# schematic.net
KiCad netlist of a schematic drawn in EAGLE
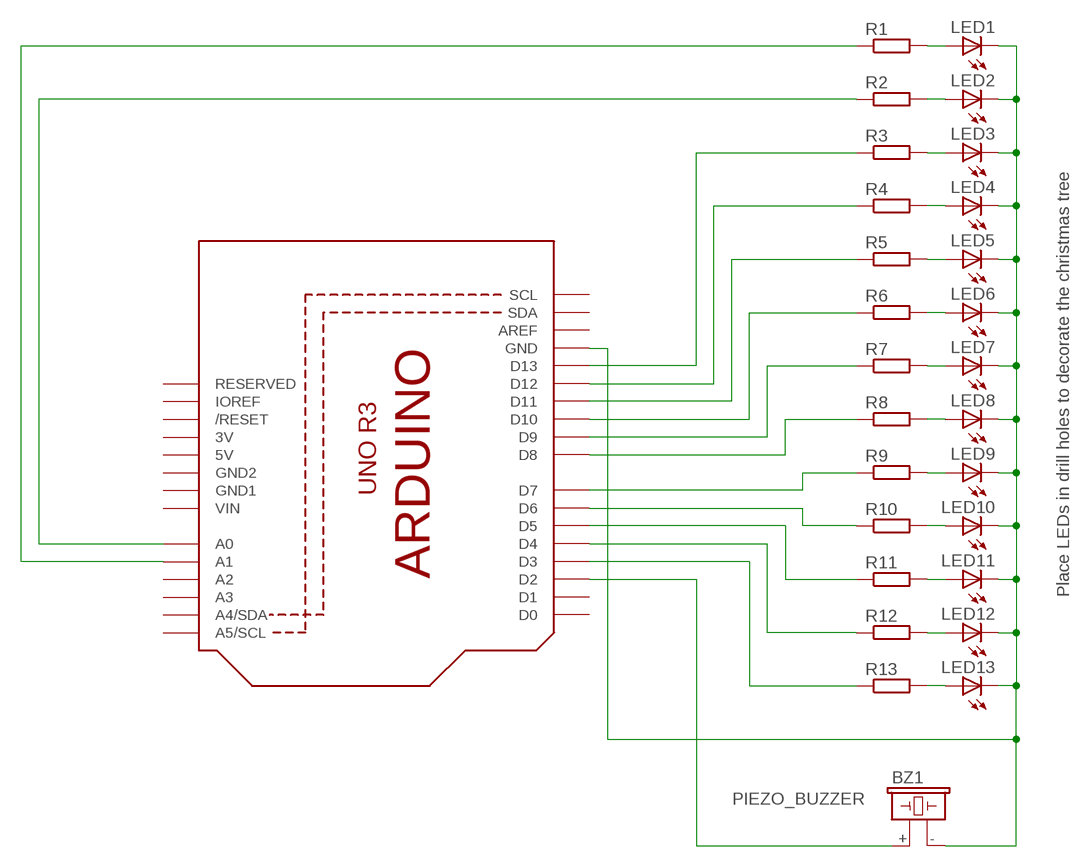
[diagram p0: schematic, sheet 1]

(export (version "E")
  (design (tool "Eeschema 10.0.6"))
  (components
    (comp (ref "BZ1")
      (value "PIEZO_BUZZER")
      (footprint "eagle-import:F_CM12P")
      (libsource (lib "eagle-import") (part "PIEZO_BUZZER"))
    )
    (comp (ref "LED1")
      (value "LED3MM")
      (footprint "eagle-import:LED3MM")
      (libsource (lib "eagle-import") (part "LED3MM"))
    )
    (comp (ref "LED2")
      (value "LED3MM")
      (footprint "eagle-import:LED3MM")
      (libsource (lib "eagle-import") (part "LED3MM"))
    )
    (comp (ref "LED3")
      (value "LED3MM")
      (footprint "eagle-import:LED3MM")
      (libsource (lib "eagle-import") (part "LED3MM"))
    )
    (comp (ref "LED4")
      (value "LED3MM")
      (footprint "eagle-import:LED3MM")
      (libsource (lib "eagle-import") (part "LED3MM"))
    )
    (comp (ref "LED5")
      (value "LED3MM")
      (footprint "eagle-import:LED3MM")
      (libsource (lib "eagle-import") (part "LED3MM"))
    )
    (comp (ref "LED6")
      (value "LED3MM")
      (footprint "eagle-import:LED3MM")
      (libsource (lib "eagle-import") (part "LED3MM"))
    )
    (comp (ref "LED7")
      (value "LED3MM")
      (footprint "eagle-import:LED3MM")
      (libsource (lib "eagle-import") (part "LED3MM"))
    )
    (comp (ref "LED8")
      (value "LED3MM")
      (footprint "eagle-import:LED3MM")
      (libsource (lib "eagle-import") (part "LED3MM"))
    )
    (comp (ref "LED9")
      (value "LED3MM")
      (footprint "eagle-import:LED3MM")
      (libsource (lib "eagle-import") (part "LED3MM"))
    )
    (comp (ref "LED10")
      (value "LED3MM")
      (footprint "eagle-import:LED3MM")
      (libsource (lib "eagle-import") (part "LED3MM"))
    )
    (comp (ref "LED11")
      (value "LED3MM")
      (footprint "eagle-import:LED3MM")
      (libsource (lib "eagle-import") (part "LED3MM"))
    )
    (comp (ref "LED12")
      (value "LED3MM")
      (footprint "eagle-import:LED3MM")
      (libsource (lib "eagle-import") (part "LED3MM"))
    )
    (comp (ref "LED13")
      (value "LED3MM")
      (footprint "eagle-import:LED3MM")
      (libsource (lib "eagle-import") (part "LED3MM"))
    )
    (comp (ref "R1")
      (value "R0204/7")
      (footprint "eagle-import:0204_7")
      (libsource (lib "eagle-import") (part "R0204/7"))
    )
    (comp (ref "R2")
      (value "R0204/7")
      (footprint "eagle-import:0204_7")
      (libsource (lib "eagle-import") (part "R0204/7"))
    )
    (comp (ref "R3")
      (value "R0204/7")
      (footprint "eagle-import:0204_7")
      (libsource (lib "eagle-import") (part "R0204/7"))
    )
    (comp (ref "R4")
      (value "R0204/7")
      (footprint "eagle-import:0204_7")
      (libsource (lib "eagle-import") (part "R0204/7"))
    )
    (comp (ref "R5")
      (value "R0204/7")
      (footprint "eagle-import:0204_7")
      (libsource (lib "eagle-import") (part "R0204/7"))
    )
    (comp (ref "R6")
      (value "R0204/7")
      (footprint "eagle-import:0204_7")
      (libsource (lib "eagle-import") (part "R0204/7"))
    )
    (comp (ref "R7")
      (value "R0204/7")
      (footprint "eagle-import:0204_7")
      (libsource (lib "eagle-import") (part "R0204/7"))
    )
    (comp (ref "R8")
      (value "R0204/7")
      (footprint "eagle-import:0204_7")
      (libsource (lib "eagle-import") (part "R0204/7"))
    )
    (comp (ref "R9")
      (value "R0204/7")
      (footprint "eagle-import:0204_7")
      (libsource (lib "eagle-import") (part "R0204/7"))
    )
    (comp (ref "R10")
      (value "R0204/7")
      (footprint "eagle-import:0204_7")
      (libsource (lib "eagle-import") (part "R0204/7"))
    )
    (comp (ref "R11")
      (value "R0204/7")
      (footprint "eagle-import:0204_7")
      (libsource (lib "eagle-import") (part "R0204/7"))
    )
    (comp (ref "R12")
      (value "R0204/7")
      (footprint "eagle-import:0204_7")
      (libsource (lib "eagle-import") (part "R0204/7"))
    )
    (comp (ref "R13")
      (value "R0204/7")
      (footprint "eagle-import:0204_7")
      (libsource (lib "eagle-import") (part "R0204/7"))
    )
    (comp (ref "U1")
      (value "ARDUINOR3-BPLACE")
      (footprint "eagle-import:ARDUINOR3-BPLACE")
      (libsource (lib "eagle-import") (part "ARDUINOR3-BPLACE"))
    )
  )
  (nets
    (net (code "1") (name "/3V") (class "Default")
      (node (ref "U1") (pin "3V") (pinfunction "3V_3V") (pintype "power_in"))
    )
    (net (code "2") (name "/5V") (class "Default")
      (node (ref "U1") (pin "5V") (pinfunction "5V_5V") (pintype "power_in"))
    )
    (net (code "3") (name "/GND1") (class "Default")
      (node (ref "U1") (pin "GND1") (pinfunction "GND1_GND1") (pintype "power_in"))
    )
    (net (code "4") (name "/GND2") (class "Default")
      (node (ref "U1") (pin "GND2") (pinfunction "GND2_GND2") (pintype "power_in"))
    )
    (net (code "5") (name "/VIN") (class "Default")
      (node (ref "U1") (pin "VIN") (pinfunction "VIN_VIN") (pintype "power_in"))
    )
    (net (code "6") (name "Net-(BZ1-1)") (class "Default")
      (node (ref "BZ1") (pin "+") (pinfunction "1_+") (pintype "passive"))
      (node (ref "U1") (pin "D2") (pinfunction "D2_D2") (pintype "bidirectional"))
    )
    (net (code "7") (name "Net-(BZ1-2)") (class "Default")
      (node (ref "BZ1") (pin "-") (pinfunction "2_-") (pintype "passive"))
      (node (ref "LED1") (pin "K") (pinfunction "C_K") (pintype "passive"))
      (node (ref "LED10") (pin "K") (pinfunction "C_K") (pintype "passive"))
      (node (ref "LED11") (pin "K") (pinfunction "C_K") (pintype "passive"))
      (node (ref "LED12") (pin "K") (pinfunction "C_K") (pintype "passive"))
      (node (ref "LED13") (pin "K") (pinfunction "C_K") (pintype "passive"))
      (node (ref "LED2") (pin "K") (pinfunction "C_K") (pintype "passive"))
      (node (ref "LED3") (pin "K") (pinfunction "C_K") (pintype "passive"))
      (node (ref "LED4") (pin "K") (pinfunction "C_K") (pintype "passive"))
      (node (ref "LED5") (pin "K") (pinfunction "C_K") (pintype "passive"))
      (node (ref "LED6") (pin "K") (pinfunction "C_K") (pintype "passive"))
      (node (ref "LED7") (pin "K") (pinfunction "C_K") (pintype "passive"))
      (node (ref "LED8") (pin "K") (pinfunction "C_K") (pintype "passive"))
      (node (ref "LED9") (pin "K") (pinfunction "C_K") (pintype "passive"))
      (node (ref "U1") (pin "GND") (pinfunction "GND_GND") (pintype "power_in"))
    )
    (net (code "8") (name "Net-(LED1-PadA)") (class "Default")
      (node (ref "LED1") (pin "A") (pinfunction "A_A") (pintype "passive"))
      (node (ref "R1") (pin "2") (pinfunction "2_2") (pintype "passive"))
    )
    (net (code "9") (name "Net-(LED2-PadA)") (class "Default")
      (node (ref "LED2") (pin "A") (pinfunction "A_A") (pintype "passive"))
      (node (ref "R2") (pin "2") (pinfunction "2_2") (pintype "passive"))
    )
    (net (code "10") (name "Net-(LED3-PadA)") (class "Default")
      (node (ref "LED3") (pin "A") (pinfunction "A_A") (pintype "passive"))
      (node (ref "R3") (pin "2") (pinfunction "2_2") (pintype "passive"))
    )
    (net (code "11") (name "Net-(LED4-PadA)") (class "Default")
      (node (ref "LED4") (pin "A") (pinfunction "A_A") (pintype "passive"))
      (node (ref "R4") (pin "2") (pinfunction "2_2") (pintype "passive"))
    )
    (net (code "12") (name "Net-(LED5-PadA)") (class "Default")
      (node (ref "LED5") (pin "A") (pinfunction "A_A") (pintype "passive"))
      (node (ref "R5") (pin "2") (pinfunction "2_2") (pintype "passive"))
    )
    (net (code "13") (name "Net-(LED6-PadA)") (class "Default")
      (node (ref "LED6") (pin "A") (pinfunction "A_A") (pintype "passive"))
      (node (ref "R6") (pin "2") (pinfunction "2_2") (pintype "passive"))
    )
    (net (code "14") (name "Net-(LED7-PadA)") (class "Default")
      (node (ref "LED7") (pin "A") (pinfunction "A_A") (pintype "passive"))
      (node (ref "R7") (pin "2") (pinfunction "2_2") (pintype "passive"))
    )
    (net (code "15") (name "Net-(LED8-PadA)") (class "Default")
      (node (ref "LED8") (pin "A") (pinfunction "A_A") (pintype "passive"))
      (node (ref "R8") (pin "2") (pinfunction "2_2") (pintype "passive"))
    )
    (net (code "16") (name "Net-(LED9-PadA)") (class "Default")
      (node (ref "LED9") (pin "A") (pinfunction "A_A") (pintype "passive"))
      (node (ref "R9") (pin "2") (pinfunction "2_2") (pintype "passive"))
    )
    (net (code "17") (name "Net-(LED10-PadA)") (class "Default")
      (node (ref "LED10") (pin "A") (pinfunction "A_A") (pintype "passive"))
      (node (ref "R10") (pin "2") (pinfunction "2_2") (pintype "passive"))
    )
    (net (code "18") (name "Net-(LED11-PadA)") (class "Default")
      (node (ref "LED11") (pin "A") (pinfunction "A_A") (pintype "passive"))
      (node (ref "R11") (pin "2") (pinfunction "2_2") (pintype "passive"))
    )
    (net (code "19") (name "Net-(LED12-PadA)") (class "Default")
      (node (ref "LED12") (pin "A") (pinfunction "A_A") (pintype "passive"))
      (node (ref "R12") (pin "2") (pinfunction "2_2") (pintype "passive"))
    )
    (net (code "20") (name "Net-(LED13-PadA)") (class "Default")
      (node (ref "LED13") (pin "A") (pinfunction "A_A") (pintype "passive"))
      (node (ref "R13") (pin "2") (pinfunction "2_2") (pintype "passive"))
    )
    (net (code "21") (name "Net-(R1-Pad1)") (class "Default")
      (node (ref "R1") (pin "1") (pinfunction "1_1") (pintype "passive"))
      (node (ref "U1") (pin "A1") (pinfunction "A1_A1") (pintype "bidirectional"))
    )
    (net (code "22") (name "Net-(R2-Pad1)") (class "Default")
      (node (ref "R2") (pin "1") (pinfunction "1_1") (pintype "passive"))
      (node (ref "U1") (pin "A0") (pinfunction "A0_A0") (pintype "bidirectional"))
    )
    (net (code "23") (name "Net-(R3-Pad1)") (class "Default")
      (node (ref "R3") (pin "1") (pinfunction "1_1") (pintype "passive"))
      (node (ref "U1") (pin "D13") (pinfunction "D13_D13") (pintype "bidirectional"))
    )
    (net (code "24") (name "Net-(R4-Pad1)") (class "Default")
      (node (ref "R4") (pin "1") (pinfunction "1_1") (pintype "passive"))
      (node (ref "U1") (pin "D12") (pinfunction "D12_D12") (pintype "bidirectional"))
    )
    (net (code "25") (name "Net-(R5-Pad1)") (class "Default")
      (node (ref "R5") (pin "1") (pinfunction "1_1") (pintype "passive"))
      (node (ref "U1") (pin "D11") (pinfunction "D11_D11") (pintype "bidirectional"))
    )
    (net (code "26") (name "Net-(R6-Pad1)") (class "Default")
      (node (ref "R6") (pin "1") (pinfunction "1_1") (pintype "passive"))
      (node (ref "U1") (pin "D10") (pinfunction "D10_D10") (pintype "bidirectional"))
    )
    (net (code "27") (name "Net-(R7-Pad1)") (class "Default")
      (node (ref "R7") (pin "1") (pinfunction "1_1") (pintype "passive"))
      (node (ref "U1") (pin "D9") (pinfunction "D9_D9") (pintype "bidirectional"))
    )
    (net (code "28") (name "Net-(R8-Pad1)") (class "Default")
      (node (ref "R8") (pin "1") (pinfunction "1_1") (pintype "passive"))
      (node (ref "U1") (pin "D8") (pinfunction "D8_D8") (pintype "bidirectional"))
    )
    (net (code "29") (name "Net-(R9-Pad1)") (class "Default")
      (node (ref "R9") (pin "1") (pinfunction "1_1") (pintype "passive"))
      (node (ref "U1") (pin "D7") (pinfunction "D7_D7") (pintype "bidirectional"))
    )
    (net (code "30") (name "Net-(R10-Pad1)") (class "Default")
      (node (ref "R10") (pin "1") (pinfunction "1_1") (pintype "passive"))
      (node (ref "U1") (pin "D6") (pinfunction "D6_D6") (pintype "bidirectional"))
    )
    (net (code "31") (name "Net-(R11-Pad1)") (class "Default")
      (node (ref "R11") (pin "1") (pinfunction "1_1") (pintype "passive"))
      (node (ref "U1") (pin "D5") (pinfunction "D5_D5") (pintype "bidirectional"))
    )
    (net (code "32") (name "Net-(R12-Pad1)") (class "Default")
      (node (ref "R12") (pin "1") (pinfunction "1_1") (pintype "passive"))
      (node (ref "U1") (pin "D4") (pinfunction "D4_D4") (pintype "bidirectional"))
    )
    (net (code "33") (name "Net-(R13-Pad1)") (class "Default")
      (node (ref "R13") (pin "1") (pinfunction "1_1") (pintype "passive"))
      (node (ref "U1") (pin "D3") (pinfunction "D3_D3") (pintype "bidirectional"))
    )
    (net (code "34") (name "unconnected-(U1-A4{slash}SDA-PadA4)") (class "Default")
      (node (ref "U1") (pin "A4") (pinfunction "A4/SDA_A4") (pintype "bidirectional"))
    )
    (net (code "35") (name "unconnected-(U1-A5{slash}SCL-PadA5)") (class "Default")
      (node (ref "U1") (pin "A5") (pinfunction "A5/SCL_A5") (pintype "bidirectional"))
    )
    (net (code "36") (name "unconnected-(U1-PadA2)") (class "Default")
      (node (ref "U1") (pin "A2") (pinfunction "A2_A2") (pintype "bidirectional"))
    )
    (net (code "37") (name "unconnected-(U1-PadA3)") (class "Default")
      (node (ref "U1") (pin "A3") (pinfunction "A3_A3") (pintype "bidirectional"))
    )
    (net (code "38") (name "unconnected-(U1-PadAREF)") (class "Default")
      (node (ref "U1") (pin "AREF") (pinfunction "AREF_AREF") (pintype "bidirectional"))
    )
    (net (code "39") (name "unconnected-(U1-PadD0)") (class "Default")
      (node (ref "U1") (pin "D0") (pinfunction "D0_D0") (pintype "bidirectional"))
    )
    (net (code "40") (name "unconnected-(U1-PadD1)") (class "Default")
      (node (ref "U1") (pin "D1") (pinfunction "D1_D1") (pintype "bidirectional"))
    )
    (net (code "41") (name "unconnected-(U1-PadIOREF)") (class "Default")
      (node (ref "U1") (pin "IOREF") (pinfunction "IOREF_IOREF") (pintype "output"))
    )
    (net (code "42") (name "unconnected-(U1-PadRESERVED)") (class "Default")
      (node (ref "U1") (pin "RESERVED") (pinfunction "RESERVED_RESERVED") (pintype "no_connect"))
    )
    (net (code "43") (name "unconnected-(U1-PadSCL)") (class "Default")
      (node (ref "U1") (pin "SCL") (pinfunction "SCL_SCL") (pintype "bidirectional"))
    )
    (net (code "44") (name "unconnected-(U1-PadSDA)") (class "Default")
      (node (ref "U1") (pin "SDA") (pinfunction "SDA_SDA") (pintype "bidirectional"))
    )
    (net (code "45") (name "unconnected-(U1-{slash}RESET-PadRESET)") (class "Default")
      (node (ref "U1") (pin "RESET") (pinfunction "/RESET_RESET") (pintype "bidirectional"))
    )
  )
)
